# DSO_ADC.net
KiCad netlist of a schematic drawn in Altium Designer
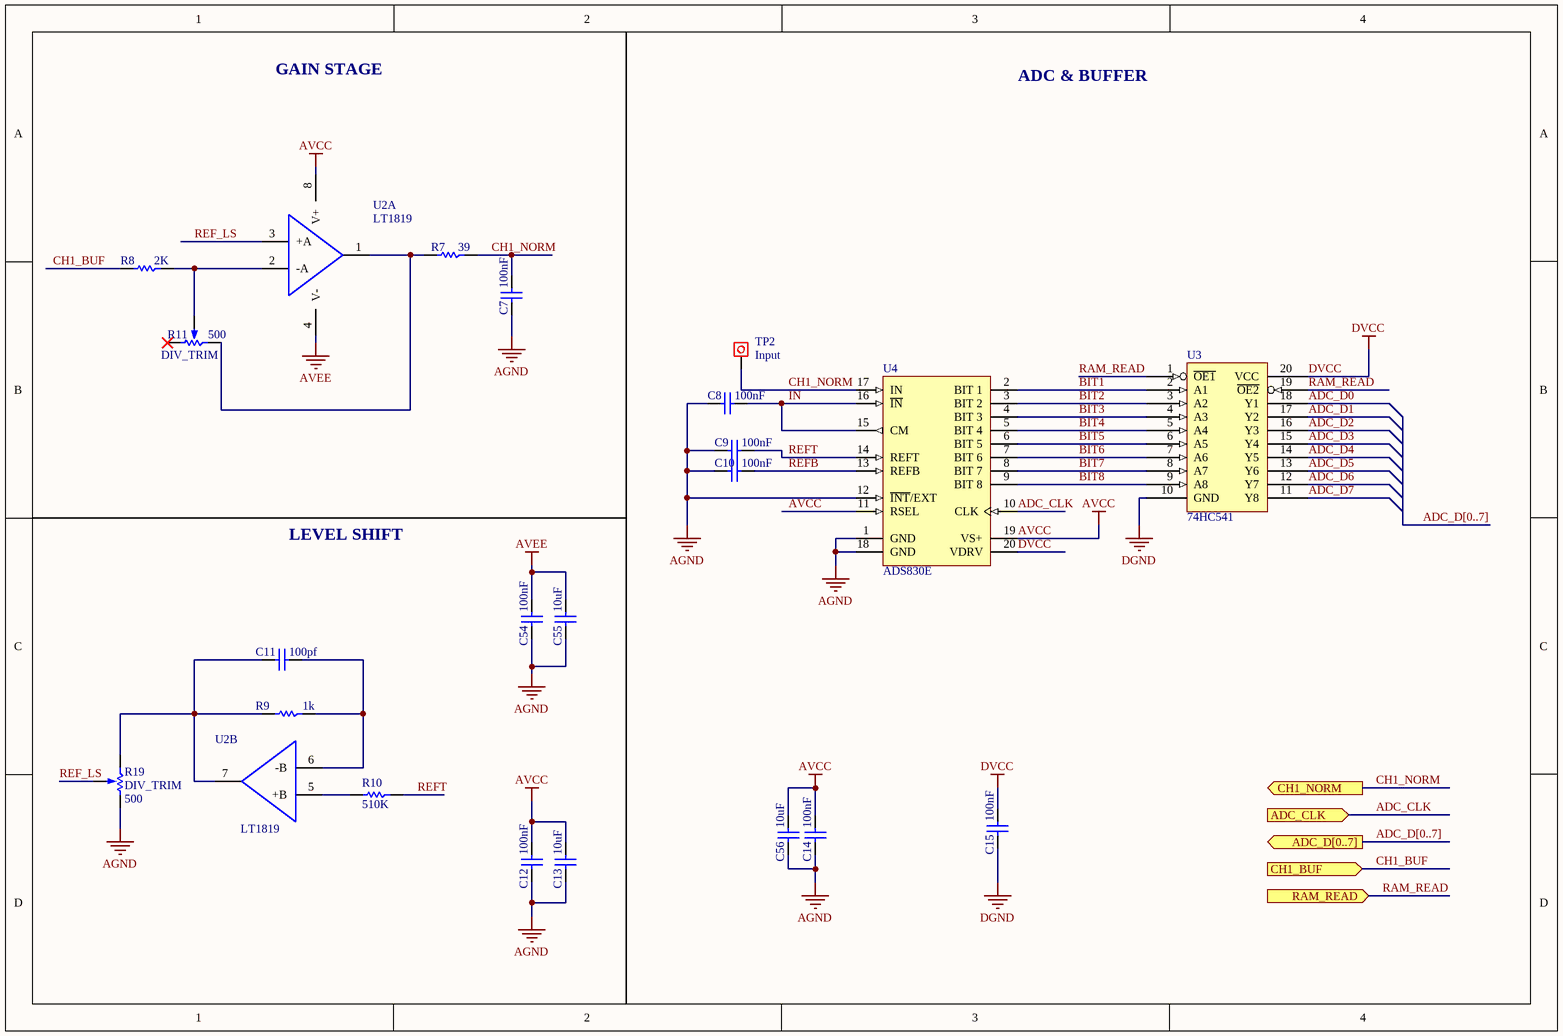
[diagram p0: DSO_ADC.SchDoc]

(export (version "E")
  (design (tool "Eeschema 10.0.6"))
  (components
    (comp (ref "C7")
      (value "100nF")
      (footprint "0805C")
      (description "Capacitor")
      (fields (field (name "REVIEWED BY") "RM - 2018/08/05"))
      (libsource (lib "DSO") (part "C"))
    )
    (comp (ref "C8")
      (value "100nF")
      (footprint "0805C")
      (description "Capacitor")
      (fields (field (name "REVIEWED BY") "RM - 2018/08/05"))
      (libsource (lib "DSO") (part "C"))
    )
    (comp (ref "C9")
      (value "100nF")
      (footprint "0805C")
      (description "Capacitor")
      (fields (field (name "REVIEWED BY") "RM - 2018/08/05"))
      (libsource (lib "DSO") (part "C"))
    )
    (comp (ref "C10")
      (value "100nF")
      (footprint "0805C")
      (description "Capacitor")
      (fields (field (name "REVIEWED BY") "RM - 2018/08/05"))
      (libsource (lib "DSO") (part "C"))
    )
    (comp (ref "C11")
      (value "100pf")
      (footprint "0805C")
      (description "Capacitor")
      (fields (field (name "REVIEWED BY") "RM - 2018/08/05"))
      (libsource (lib "DSO") (part "C"))
    )
    (comp (ref "C12")
      (value "100nF")
      (footprint "0805C")
      (description "Capacitor")
      (fields (field (name "REVIEWED BY") "RM - 2018/08/05"))
      (libsource (lib "DSO") (part "C"))
    )
    (comp (ref "C13")
      (value "10uF")
      (footprint "0805C")
      (description "Capacitor")
      (fields (field (name "REVIEWED BY") "RM - 2018/08/05"))
      (libsource (lib "DSO") (part "C"))
    )
    (comp (ref "C14")
      (value "100nF")
      (footprint "0805C")
      (description "Capacitor")
      (fields (field (name "REVIEWED BY") "RM - 2018/08/05"))
      (libsource (lib "DSO") (part "C"))
    )
    (comp (ref "C15")
      (value "100nF")
      (footprint "0805C")
      (description "Capacitor")
      (fields (field (name "REVIEWED BY") "RM - 2018/08/05"))
      (libsource (lib "DSO") (part "C"))
    )
    (comp (ref "C54")
      (value "100nF")
      (footprint "0805C")
      (description "Capacitor")
      (fields (field (name "REVIEWED BY") "RM - 2018/08/05"))
      (libsource (lib "DSO") (part "C"))
    )
    (comp (ref "C55")
      (value "10uF")
      (footprint "0805C")
      (description "Capacitor")
      (fields (field (name "REVIEWED BY") "RM - 2018/08/05"))
      (libsource (lib "DSO") (part "C"))
    )
    (comp (ref "C56")
      (value "10uF")
      (footprint "0805C")
      (description "Capacitor")
      (fields (field (name "REVIEWED BY") "RM - 2018/08/05"))
      (libsource (lib "DSO") (part "C"))
    )
    (comp (ref "R7")
      (value "39")
      (footprint "0805")
      (description "Resistor")
      (fields (field (name "REVIEWED BY") "RM - 2018/08/05"))
      (libsource (lib "DSO") (part "R"))
    )
    (comp (ref "R8")
      (value "2K")
      (footprint "0805")
      (description "Resistor")
      (fields (field (name "REVIEWED BY") "RM - 2018/08/05"))
      (libsource (lib "DSO") (part "R"))
    )
    (comp (ref "R9")
      (value "1k")
      (footprint "0805")
      (description "Resistor")
      (fields (field (name "REVIEWED BY") "RM - 2018/08/05"))
      (libsource (lib "DSO") (part "R"))
    )
    (comp (ref "R10")
      (value "510K")
      (footprint "0805")
      (description "Resistor")
      (fields (field (name "REVIEWED BY") "RM - 2018/08/05"))
      (libsource (lib "DSO") (part "R"))
    )
    (comp (ref "R11")
      (value "DIV_TRIM")
      (footprint "RPOT")
      (description "Variable Resistor")
      (fields (field (name "ALTIUM_VALUE") "500"))
      (libsource (lib "RPOT") (part "RV"))
    )
    (comp (ref "R19")
      (value "DIV_TRIM")
      (footprint "RPOT")
      (description "Variable Resistor")
      (fields (field (name "ALTIUM_VALUE") "500"))
      (libsource (lib "RPOT") (part "RV"))
    )
    (comp (ref "TP2")
      (value "Input")
      (footprint "Testpoin")
      (description "Pad")
      (fields (field (name "Comment") "INPUT"))
      (libsource (lib "DSO") (part "Test Point"))
    )
    (comp (ref "U2")
      (value "LT1819")
      (footprint "SOIC-8")
      (description "OpAmp High Frequency Dual")
      (fields (field (name "REVIEWED BY") "RM - 2018/08/05"))
      (libsource (lib "DSO") (part "LT1819"))
    )
    (comp (ref "U3")
      (value "74HC541")
      (footprint "SOT163-1_N")
      (description "(ADV) Octal Buffer, Line Driver")
      (fields (field (name "REVIEWED BY") "RM - 2018/08/05"))
      (libsource (lib "DSO") (part "74HC541"))
    )
    (comp (ref "U4")
      (value "ADS830E")
      (footprint "TI-DBQ20_L")
      (fields (field (name "REVIEWED BY") "RM - 2018/08/05"))
      (libsource (lib "DSO") (part "ADS830E"))
    )
  )
  (nets
    (net (code "1") (name "/ADC_CLK") (class "Default")
      (node (ref "U4") (pin "10") (pinfunction "CLK_10") (pintype "input"))
    )
    (net (code "2") (name "/ADC_D0") (class "Default")
      (node (ref "U3") (pin "18") (pinfunction "Y1_18") (pintype "tri_state"))
    )
    (net (code "3") (name "/ADC_D1") (class "Default")
      (node (ref "U3") (pin "17") (pinfunction "Y2_17") (pintype "tri_state"))
    )
    (net (code "4") (name "/ADC_D2") (class "Default")
      (node (ref "U3") (pin "16") (pinfunction "Y3_16") (pintype "tri_state"))
    )
    (net (code "5") (name "/ADC_D3") (class "Default")
      (node (ref "U3") (pin "15") (pinfunction "Y4_15") (pintype "tri_state"))
    )
    (net (code "6") (name "/ADC_D4") (class "Default")
      (node (ref "U3") (pin "14") (pinfunction "Y5_14") (pintype "tri_state"))
    )
    (net (code "7") (name "/ADC_D5") (class "Default")
      (node (ref "U3") (pin "13") (pinfunction "Y6_13") (pintype "tri_state"))
    )
    (net (code "8") (name "/ADC_D6") (class "Default")
      (node (ref "U3") (pin "12") (pinfunction "Y7_12") (pintype "tri_state"))
    )
    (net (code "9") (name "/ADC_D7") (class "Default")
      (node (ref "U3") (pin "11") (pinfunction "Y8_11") (pintype "tri_state"))
    )
    (net (code "11") (name "/BIT1") (class "Default")
      (node (ref "U3") (pin "2") (pinfunction "A1_2") (pintype "input"))
      (node (ref "U4") (pin "2") (pinfunction "BIT_1_2") (pintype "tri_state"))
    )
    (net (code "12") (name "/BIT2") (class "Default")
      (node (ref "U3") (pin "3") (pinfunction "A2_3") (pintype "input"))
      (node (ref "U4") (pin "3") (pinfunction "BIT_2_3") (pintype "tri_state"))
    )
    (net (code "13") (name "/BIT3") (class "Default")
      (node (ref "U3") (pin "4") (pinfunction "A3_4") (pintype "input"))
      (node (ref "U4") (pin "4") (pinfunction "BIT_3_4") (pintype "tri_state"))
    )
    (net (code "14") (name "/BIT4") (class "Default")
      (node (ref "U3") (pin "5") (pinfunction "A4_5") (pintype "input"))
      (node (ref "U4") (pin "5") (pinfunction "BIT_4_5") (pintype "tri_state"))
    )
    (net (code "15") (name "/BIT5") (class "Default")
      (node (ref "U3") (pin "6") (pinfunction "A5_6") (pintype "input"))
      (node (ref "U4") (pin "6") (pinfunction "BIT_5_6") (pintype "tri_state"))
    )
    (net (code "16") (name "/BIT6") (class "Default")
      (node (ref "U3") (pin "7") (pinfunction "A6_7") (pintype "input"))
      (node (ref "U4") (pin "7") (pinfunction "BIT_6_7") (pintype "tri_state"))
    )
    (net (code "17") (name "/BIT7") (class "Default")
      (node (ref "U3") (pin "8") (pinfunction "A7_8") (pintype "input"))
      (node (ref "U4") (pin "8") (pinfunction "BIT_7_8") (pintype "tri_state"))
    )
    (net (code "18") (name "/BIT8") (class "Default")
      (node (ref "U3") (pin "9") (pinfunction "A8_9") (pintype "input"))
      (node (ref "U4") (pin "9") (pinfunction "BIT_8_9") (pintype "tri_state"))
    )
    (net (code "19") (name "/CH1_BUF") (class "Default") (node (ref "R8") (pin "2") (pintype "passive")))
    (net (code "20") (name "/CH1_NORM") (class "Default")
      (node (ref "C7") (pin "1") (pinfunction "1_1") (pintype "passive"))
      (node (ref "R7") (pin "1") (pintype "passive"))
      (node (ref "TP2") (pin "1") (pintype "passive"))
      (node (ref "U4") (pin "17") (pinfunction "IN_17") (pintype "input"))
    )
    (net (code "21") (name "/I~{N}") (class "Default")
      (node (ref "C8") (pin "1") (pinfunction "1_1") (pintype "passive"))
      (node (ref "U4") (pin "15") (pinfunction "CM_15") (pintype "output"))
      (node (ref "U4") (pin "16") (pinfunction "~{IN}_16") (pintype "input"))
    )
    (net (code "22") (name "/RAM_READ") (class "Default")
      (node (ref "U3") (pin "1") (pinfunction "~{OE1}_1") (pintype "input"))
      (node (ref "U3") (pin "19") (pinfunction "~{OE2}_19") (pintype "input"))
    )
    (net (code "23") (name "/REFB") (class "Default")
      (node (ref "C10") (pin "1") (pinfunction "1_1") (pintype "passive"))
      (node (ref "U4") (pin "13") (pinfunction "REFB_13") (pintype "input"))
    )
    (net (code "24") (name "/REFT") (class "Default")
      (node (ref "C9") (pin "1") (pinfunction "1_1") (pintype "passive"))
      (node (ref "R10") (pin "1") (pintype "passive"))
      (node (ref "U4") (pin "14") (pinfunction "REFT_14") (pintype "input"))
    )
    (net (code "25") (name "/REF_LS") (class "Default")
      (node (ref "R19") (pin "2") (pintype "passive"))
      (node (ref "U2") (pin "3") (pinfunction "+A_3") (pintype "passive"))
    )
    (net (code "26") (name "AGND") (class "Default")
      (node (ref "C10") (pin "2") (pinfunction "2_2") (pintype "passive"))
      (node (ref "C12") (pin "2") (pinfunction "2_2") (pintype "passive"))
      (node (ref "C13") (pin "2") (pinfunction "2_2") (pintype "passive"))
      (node (ref "C14") (pin "2") (pinfunction "2_2") (pintype "passive"))
      (node (ref "C54") (pin "2") (pinfunction "2_2") (pintype "passive"))
      (node (ref "C55") (pin "2") (pinfunction "2_2") (pintype "passive"))
      (node (ref "C56") (pin "2") (pinfunction "2_2") (pintype "passive"))
      (node (ref "C7") (pin "2") (pinfunction "2_2") (pintype "passive"))
      (node (ref "C8") (pin "2") (pinfunction "2_2") (pintype "passive"))
      (node (ref "C9") (pin "2") (pinfunction "2_2") (pintype "passive"))
      (node (ref "R19") (pin "3") (pintype "passive"))
      (node (ref "U4") (pin "1") (pinfunction "GND_1") (pintype "power_in"))
      (node (ref "U4") (pin "12") (pinfunction "~{INT}/EXT_12") (pintype "input"))
      (node (ref "U4") (pin "18") (pinfunction "GND_18") (pintype "power_in"))
    )
    (net (code "27") (name "AVCC") (class "Default")
      (node (ref "C12") (pin "1") (pinfunction "1_1") (pintype "passive"))
      (node (ref "C13") (pin "1") (pinfunction "1_1") (pintype "passive"))
      (node (ref "C14") (pin "1") (pinfunction "1_1") (pintype "passive"))
      (node (ref "C56") (pin "1") (pinfunction "1_1") (pintype "passive"))
      (node (ref "U2") (pin "8") (pinfunction "V+_8") (pintype "passive"))
      (node (ref "U4") (pin "11") (pinfunction "RSEL_11") (pintype "input"))
      (node (ref "U4") (pin "19") (pinfunction "VS+_19") (pintype "power_in"))
    )
    (net (code "28") (name "AVEE") (class "Default")
      (node (ref "C54") (pin "1") (pinfunction "1_1") (pintype "passive"))
      (node (ref "C55") (pin "1") (pinfunction "1_1") (pintype "passive"))
      (node (ref "U2") (pin "4") (pinfunction "V-_4") (pintype "passive"))
    )
    (net (code "29") (name "DGND") (class "Default")
      (node (ref "C15") (pin "2") (pinfunction "2_2") (pintype "passive"))
      (node (ref "U3") (pin "10") (pinfunction "GND_10") (pintype "power_in"))
    )
    (net (code "30") (name "DVCC") (class "Default")
      (node (ref "C15") (pin "1") (pinfunction "1_1") (pintype "passive"))
      (node (ref "U3") (pin "20") (pinfunction "VCC_20") (pintype "power_in"))
      (node (ref "U4") (pin "20") (pinfunction "VDRV_20") (pintype "power_in"))
    )
    (net (code "31") (name "Net-(U2A--A)") (class "Default")
      (node (ref "R11") (pin "2") (pintype "passive"))
      (node (ref "R8") (pin "1") (pintype "passive"))
      (node (ref "U2") (pin "2") (pinfunction "-A_2") (pintype "passive"))
    )
    (net (code "32") (name "Net-(U2A-OUTA)") (class "Default")
      (node (ref "R11") (pin "1") (pintype "passive"))
      (node (ref "R7") (pin "2") (pintype "passive"))
      (node (ref "U2") (pin "1") (pinfunction "OUTA_1") (pintype "passive"))
    )
    (net (code "33") (name "Net-(U2B-+B)") (class "Default")
      (node (ref "R10") (pin "2") (pintype "passive"))
      (node (ref "U2") (pin "5") (pinfunction "+B_5") (pintype "passive"))
    )
    (net (code "34") (name "Net-(U2B--B)") (class "Default")
      (node (ref "C11") (pin "1") (pinfunction "1_1") (pintype "passive"))
      (node (ref "R9") (pin "1") (pintype "passive"))
      (node (ref "U2") (pin "6") (pinfunction "-B_6") (pintype "passive"))
    )
    (net (code "35") (name "Net-(U2B-OUTB)") (class "Default")
      (node (ref "C11") (pin "2") (pinfunction "2_2") (pintype "passive"))
      (node (ref "R19") (pin "1") (pintype "passive"))
      (node (ref "R9") (pin "2") (pintype "passive"))
      (node (ref "U2") (pin "7") (pinfunction "OUTB_7") (pintype "passive"))
    )
    (net (code "36") (name "unconnected-(R11-Pad3)") (class "Default")
      (node (ref "R11") (pin "3") (pintype "passive+no_connect"))
    )
  )
)
